# Sheet1.net
KiCad netlist of a schematic drawn in Altium Designer
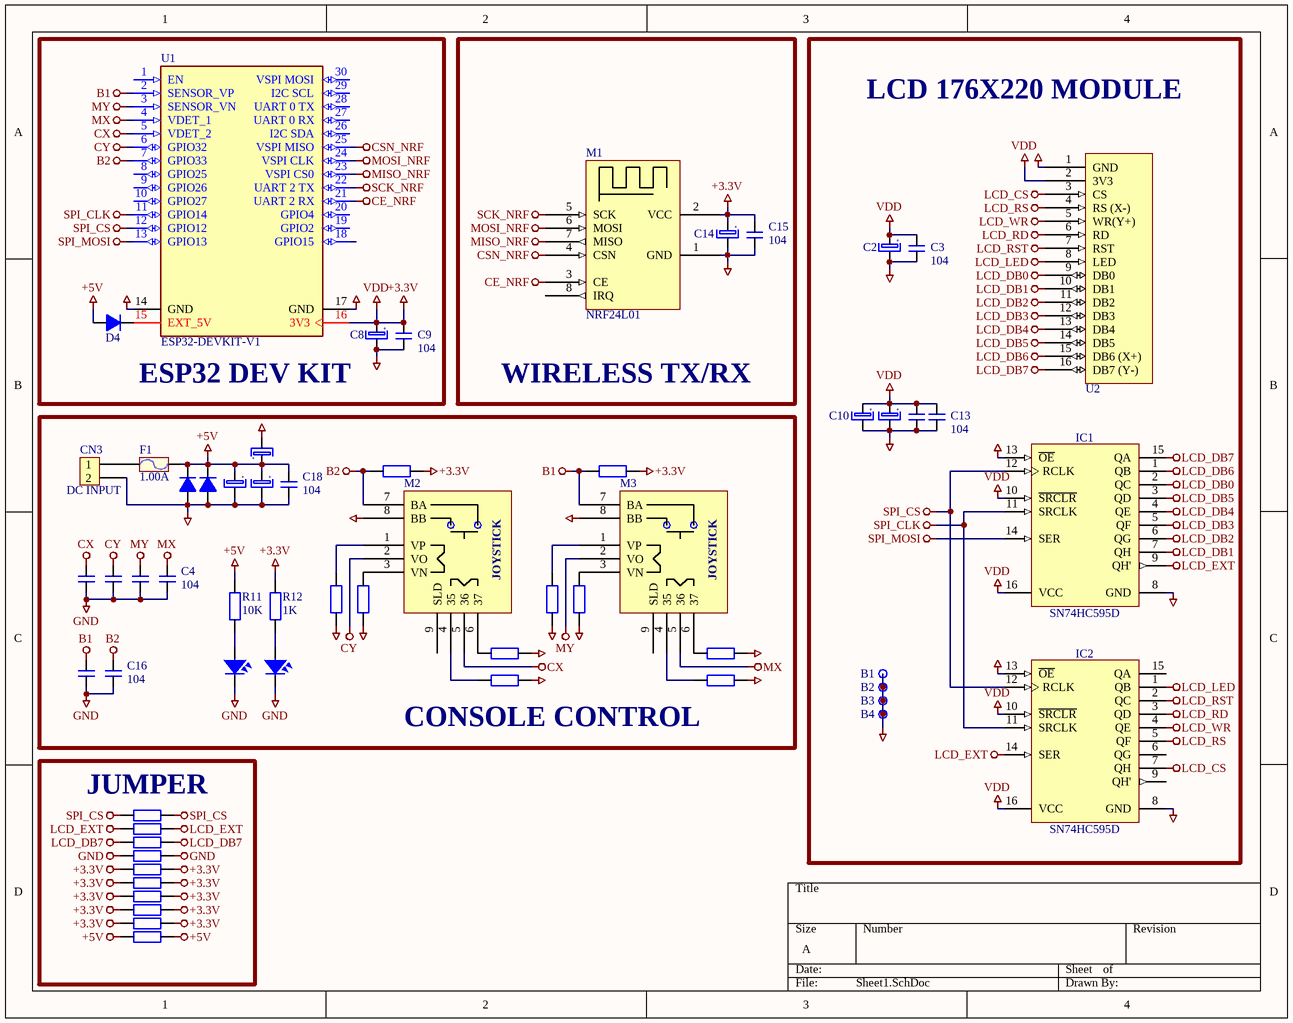
[diagram p0: Sheet1.SchDoc]

(export (version "E")
  (design (tool "Eeschema 10.0.6"))
  (components
    (comp (ref "B1")
      (value "Plated Hole")
      (footprint "MTG300_600")
      (description "Single Terminal Socket")
      (fields (field (name "PART NUMBER") "PLATED_HOLE3.0_PAD6.0") (field (name "AUTHOR") "CERN DEM JLC"))
      (libsource (lib "Eletro-mechanical") (part "Single Terminal Socket"))
    )
    (comp (ref "B2")
      (value "Plated Hole")
      (footprint "MTG300_600")
      (description "Single Terminal Socket")
      (fields (field (name "PART NUMBER") "PLATED_HOLE3.0_PAD6.0") (field (name "AUTHOR") "CERN DEM JLC"))
      (libsource (lib "Eletro-mechanical") (part "Single Terminal Socket"))
    )
    (comp (ref "B3")
      (value "Plated Hole")
      (footprint "MTG300_600")
      (description "Single Terminal Socket")
      (fields (field (name "PART NUMBER") "PLATED_HOLE3.0_PAD6.0") (field (name "AUTHOR") "CERN DEM JLC"))
      (libsource (lib "Eletro-mechanical") (part "Single Terminal Socket"))
    )
    (comp (ref "B4")
      (value "Plated Hole")
      (footprint "MTG300_600")
      (description "Single Terminal Socket")
      (fields (field (name "PART NUMBER") "PLATED_HOLE3.0_PAD6.0") (field (name "AUTHOR") "CERN DEM JLC"))
      (libsource (lib "Eletro-mechanical") (part "Single Terminal Socket"))
    )
    (comp (ref "C1")
      (value "470uF")
      (footprint "Cap-P-2.5/6.3")
      (description "Polarized capacitor")
      (libsource (lib "Library") (part "Cap-Pol-Dip"))
    )
    (comp (ref "C2")
      (value "220uF")
      (footprint "Cap-P-2.5/5")
      (description "Polarized capacitor")
      (libsource (lib "Library") (part "Cap-Pol-Dip"))
    )
    (comp (ref "C3")
      (value "104")
      (footprint "Cap-Non-150mil")
      (description "Non-polar capacitor")
      (libsource (lib "Library") (part "Cap-Non-Dip"))
    )
    (comp (ref "C4")
      (value "104")
      (footprint "CAP-SMD-0805")
      (description "Non-polar capacitor")
      (libsource (lib "Library") (part "Cap-Non-SMD"))
    )
    (comp (ref "C5")
      (value "104")
      (footprint "CAP-SMD-0805")
      (description "Non-polar capacitor")
      (libsource (lib "Library") (part "Cap-Non-SMD"))
    )
    (comp (ref "C6")
      (value "104")
      (footprint "CAP-SMD-0805")
      (description "Non-polar capacitor")
      (libsource (lib "Library") (part "Cap-Non-SMD"))
    )
    (comp (ref "C7")
      (value "104")
      (footprint "CAP-SMD-0805")
      (description "Non-polar capacitor")
      (libsource (lib "Library") (part "Cap-Non-SMD"))
    )
    (comp (ref "C8")
      (value "220uF")
      (footprint "Cap-P-2.5/5")
      (description "Polarized capacitor")
      (libsource (lib "Library") (part "Cap-Pol-Dip"))
    )
    (comp (ref "C9")
      (value "104")
      (footprint "Cap-Non-150mil")
      (description "Non-polar capacitor")
      (libsource (lib "Library") (part "Cap-Non-Dip"))
    )
    (comp (ref "C10")
      (value "220uF")
      (footprint "Cap-P-2.5/5")
      (description "Polarized capacitor")
      (libsource (lib "Library") (part "Cap-Pol-Dip"))
    )
    (comp (ref "C11")
      (value "220uF")
      (footprint "Cap-P-2.5/5")
      (description "Polarized capacitor")
      (libsource (lib "Library") (part "Cap-Pol-Dip"))
    )
    (comp (ref "C12")
      (value "104")
      (footprint "Cap-Non-150mil")
      (description "Non-polar capacitor")
      (libsource (lib "Library") (part "Cap-Non-Dip"))
    )
    (comp (ref "C13")
      (value "104")
      (footprint "Cap-Non-150mil")
      (description "Non-polar capacitor")
      (libsource (lib "Library") (part "Cap-Non-Dip"))
    )
    (comp (ref "C14")
      (value "220uF")
      (footprint "Cap-P-2.5/5")
      (description "Polarized capacitor")
      (libsource (lib "Library") (part "Cap-Pol-Dip"))
    )
    (comp (ref "C15")
      (value "104")
      (footprint "Cap-Non-150mil")
      (description "Non-polar capacitor")
      (libsource (lib "Library") (part "Cap-Non-Dip"))
    )
    (comp (ref "C16")
      (value "104")
      (footprint "CAP-SMD-0805")
      (description "Non-polar capacitor")
      (libsource (lib "Library") (part "Cap-Non-SMD"))
    )
    (comp (ref "C17")
      (value "104")
      (footprint "CAP-SMD-0805")
      (description "Non-polar capacitor")
      (libsource (lib "Library") (part "Cap-Non-SMD"))
    )
    (comp (ref "C18")
      (value "104")
      (footprint "Cap-Non-150mil")
      (description "Non-polar capacitor")
      (libsource (lib "Library") (part "Cap-Non-Dip"))
    )
    (comp (ref "C19")
      (value "470uF")
      (footprint "Cap-P-2.5/6.3")
      (description "Polarized capacitor")
      (libsource (lib "Library") (part "Cap-Pol-Dip"))
    )
    (comp (ref "C20")
      (value "470uF")
      (footprint "Cap-P-2.5/6.3")
      (description "Polarized capacitor")
      (libsource (lib "Library") (part "Cap-Pol-Dip"))
    )
    (comp (ref "CN3") (value "DC INPUT") (footprint "KF2/5.08") (libsource (lib "Library") (part "KF 2")))
    (comp (ref "D1")
      (value "SS14")
      (footprint "SOD 106")
      (description "Diode SMD")
      (libsource (lib "Library") (part "Diode SMD"))
    )
    (comp (ref "D2")
      (value "SS14")
      (footprint "SOD 106")
      (description "Diode SMD")
      (libsource (lib "Library") (part "Diode SMD"))
    )
    (comp (ref "D4")
      (value "SS14")
      (footprint "SOD 106")
      (description "Diode SMD")
      (libsource (lib "Library") (part "Diode SMD"))
    )
    (comp (ref "F1") (value "1.00A") (footprint "Fuse-Dip1") (libsource (lib "Library") (part "Fuse Dip")))
    (comp (ref "IC1")
      (value "SN74HC595D")
      (footprint "SOIC127P600X175-16N")
      (description "8-Bit Shift Register With 3-State Output Register")
      (fields (field (name "MANUFACTURER") "TEXAS INSTRUMENTS") (field (name "AUTHOR") "CERN DEM JLC"))
      (libsource (lib "ICs And Semiconductors") (part "74595"))
    )
    (comp (ref "IC2")
      (value "SN74HC595D")
      (footprint "SOIC127P600X175-16N")
      (description "8-Bit Shift Register With 3-State Output Register")
      (fields (field (name "MANUFACTURER") "TEXAS INSTRUMENTS") (field (name "AUTHOR") "CERN DEM JLC"))
      (libsource (lib "ICs And Semiconductors") (part "74595"))
    )
    (comp (ref "LED1") (value "POWER") (footprint "LED-0805") (libsource (lib "Library") (part "LED_SMD")))
    (comp (ref "LED2") (value "ESP-3.3V") (footprint "LED-0805") (libsource (lib "Library") (part "LED_SMD")))
    (comp (ref "M1")
      (value "NRF24L01")
      (footprint "NRF24L01P_M")
      (libsource (lib "TOAN_VERSION_1_0") (part "NRF24L01"))
    )
    (comp (ref "M2")
      (value "JOYSTICK")
      (footprint "JOYSTICK")
      (libsource (lib "TOAN_VERSION_1_0") (part "JOYSTICK"))
    )
    (comp (ref "M3")
      (value "JOYSTICK")
      (footprint "JOYSTICK")
      (libsource (lib "TOAN_VERSION_1_0") (part "JOYSTICK"))
    )
    (comp (ref "R1")
      (value "1K")
      (footprint "RES-SMD-0805")
      (description "Resistor SMD")
      (libsource (lib "Library") (part "Res SMD"))
    )
    (comp (ref "R2")
      (value "1K")
      (footprint "RES-SMD-0805")
      (description "Resistor SMD")
      (libsource (lib "Library") (part "Res SMD"))
    )
    (comp (ref "R3")
      (value "1K")
      (footprint "RES-SMD-0805")
      (description "Resistor SMD")
      (libsource (lib "Library") (part "Res SMD"))
    )
    (comp (ref "R4")
      (value "1K")
      (footprint "RES-SMD-0805")
      (description "Resistor SMD")
      (libsource (lib "Library") (part "Res SMD"))
    )
    (comp (ref "R5")
      (value "1K")
      (footprint "RES-SMD-0805")
      (description "Resistor SMD")
      (libsource (lib "Library") (part "Res SMD"))
    )
    (comp (ref "R6")
      (value "1K")
      (footprint "RES-SMD-0805")
      (description "Resistor SMD")
      (libsource (lib "Library") (part "Res SMD"))
    )
    (comp (ref "R7")
      (value "1K")
      (footprint "RES-SMD-0805")
      (description "Resistor SMD")
      (libsource (lib "Library") (part "Res SMD"))
    )
    (comp (ref "R8")
      (value "1K")
      (footprint "RES-SMD-0805")
      (description "Resistor SMD")
      (libsource (lib "Library") (part "Res SMD"))
    )
    (comp (ref "R9")
      (value "1K")
      (footprint "RES-SMD-0805")
      (description "Resistor SMD")
      (libsource (lib "Library") (part "Res SMD"))
    )
    (comp (ref "R10")
      (value "1K")
      (footprint "RES-SMD-0805")
      (description "Resistor SMD")
      (libsource (lib "Library") (part "Res SMD"))
    )
    (comp (ref "R11")
      (value "10K")
      (footprint "RES-SMD-0805")
      (description "Resistor SMD")
      (libsource (lib "Library") (part "Res SMD"))
    )
    (comp (ref "R12")
      (value "1K")
      (footprint "RES-SMD-0805")
      (description "Resistor SMD")
      (libsource (lib "Library") (part "Res SMD"))
    )
    (comp (ref "R13")
      (value "0R")
      (footprint "RES-SMD-0805")
      (description "Resistor SMD")
      (libsource (lib "Library") (part "Res SMD"))
    )
    (comp (ref "R14")
      (value "0R")
      (footprint "RES-SMD-0805")
      (description "Resistor SMD")
      (libsource (lib "Library") (part "Res SMD"))
    )
    (comp (ref "R15")
      (value "0R")
      (footprint "RES-SMD-0805")
      (description "Resistor SMD")
      (libsource (lib "Library") (part "Res SMD"))
    )
    (comp (ref "R16")
      (value "0R")
      (footprint "RES-SMD-1206")
      (description "Resistor SMD")
      (libsource (lib "Library") (part "Res SMD"))
    )
    (comp (ref "R17")
      (value "0R")
      (footprint "RES-SMD-1206")
      (description "Resistor SMD")
      (libsource (lib "Library") (part "Res SMD"))
    )
    (comp (ref "R18")
      (value "0R")
      (footprint "RES-SMD-1206")
      (description "Resistor SMD")
      (libsource (lib "Library") (part "Res SMD"))
    )
    (comp (ref "R19")
      (value "0R")
      (footprint "RES-SMD-2512")
      (description "Resistor SMD")
      (libsource (lib "Library") (part "Res SMD"))
    )
    (comp (ref "R20")
      (value "0R")
      (footprint "RES-SMD-2512")
      (description "Resistor SMD")
      (libsource (lib "Library") (part "Res SMD"))
    )
    (comp (ref "R21")
      (value "0R")
      (footprint "RES-SMD-2512")
      (description "Resistor SMD")
      (libsource (lib "Library") (part "Res SMD"))
    )
    (comp (ref "R22")
      (value "0R")
      (footprint "RES-SMD-2512")
      (description "Resistor SMD")
      (libsource (lib "Library") (part "Res SMD"))
    )
    (comp (ref "U1")
      (value "ESP32-DEVKIT-V1")
      (footprint "MODULE_ESP32-DEVKITC-32D")
      (fields (field (name "MF") "Espressif Systems") (field (name "MP") "ESP32-DEVKITC-32D"))
      (libsource (lib "TOAN_VERSION_1_0") (part "ESP32-DEVKIT-V1"))
    )
    (comp (ref "U2")
      (value "ST7775R_2.0")
      (footprint "LCD_176X220_MODULE")
      (libsource (lib "TOAN_VERSION_1_0") (part "LCD_176x220_ST7775R"))
    )
  )
  (nets
    (net (code "1") (name "+3.3V") (class "Default")
      (node (ref "C10") (pin "1") (pinfunction "1_1") (pintype "passive"))
      (node (ref "C11") (pin "1") (pinfunction "1_1") (pintype "passive"))
      (node (ref "C12") (pin "2") (pinfunction "2_2") (pintype "passive"))
      (node (ref "C13") (pin "2") (pinfunction "2_2") (pintype "passive"))
      (node (ref "C14") (pin "1") (pinfunction "1_1") (pintype "passive"))
      (node (ref "C15") (pin "2") (pinfunction "2_2") (pintype "passive"))
      (node (ref "C2") (pin "1") (pinfunction "1_1") (pintype "passive"))
      (node (ref "C3") (pin "2") (pinfunction "2_2") (pintype "passive"))
      (node (ref "C8") (pin "1") (pinfunction "1_1") (pintype "passive"))
      (node (ref "C9") (pin "2") (pinfunction "2_2") (pintype "passive"))
      (node (ref "IC1") (pin "10") (pinfunction "~{SRCLR}_10") (pintype "input"))
      (node (ref "IC1") (pin "16") (pinfunction "VCC_16") (pintype "power_in"))
      (node (ref "IC2") (pin "10") (pinfunction "~{SRCLR}_10") (pintype "input"))
      (node (ref "IC2") (pin "16") (pinfunction "VCC_16") (pintype "power_in"))
      (node (ref "M1") (pin "2") (pinfunction "VCC_2") (pintype "passive"))
      (node (ref "R1") (pin "2") (pinfunction "2_2") (pintype "passive"))
      (node (ref "R12") (pin "2") (pinfunction "2_2") (pintype "passive"))
      (node (ref "R17") (pin "1") (pinfunction "1_1") (pintype "passive"))
      (node (ref "R17") (pin "2") (pinfunction "2_2") (pintype "passive"))
      (node (ref "R18") (pin "1") (pinfunction "1_1") (pintype "passive"))
      (node (ref "R18") (pin "2") (pinfunction "2_2") (pintype "passive"))
      (node (ref "R19") (pin "1") (pinfunction "1_1") (pintype "passive"))
      (node (ref "R19") (pin "2") (pinfunction "2_2") (pintype "passive"))
      (node (ref "R2") (pin "2") (pinfunction "2_2") (pintype "passive"))
      (node (ref "R20") (pin "1") (pinfunction "1_1") (pintype "passive"))
      (node (ref "R20") (pin "2") (pinfunction "2_2") (pintype "passive"))
      (node (ref "R21") (pin "1") (pinfunction "1_1") (pintype "passive"))
      (node (ref "R21") (pin "2") (pinfunction "2_2") (pintype "passive"))
      (node (ref "R4") (pin "1") (pinfunction "1_1") (pintype "passive"))
      (node (ref "R6") (pin "1") (pinfunction "1_1") (pintype "passive"))
      (node (ref "R7") (pin "1") (pinfunction "1_1") (pintype "passive"))
      (node (ref "R8") (pin "1") (pinfunction "1_1") (pintype "passive"))
      (node (ref "U1") (pin "16") (pinfunction "3V3_16") (pintype "power_in"))
      (node (ref "U2") (pin "2") (pinfunction "3V3_2") (pintype "power_in"))
    )
    (net (code "2") (name "+5V") (class "Default")
      (node (ref "C1") (pin "1") (pinfunction "1_1") (pintype "passive"))
      (node (ref "C18") (pin "2") (pinfunction "2_2") (pintype "passive"))
      (node (ref "C19") (pin "1") (pinfunction "1_1") (pintype "passive"))
      (node (ref "C20") (pin "1") (pinfunction "1_1") (pintype "passive"))
      (node (ref "D1") (pin "2") (pinfunction "K_2") (pintype "passive"))
      (node (ref "D2") (pin "2") (pinfunction "K_2") (pintype "passive"))
      (node (ref "D4") (pin "1") (pinfunction "A_1") (pintype "passive"))
      (node (ref "F1") (pin "2") (pinfunction "2_2") (pintype "passive"))
      (node (ref "R11") (pin "2") (pinfunction "2_2") (pintype "passive"))
      (node (ref "R22") (pin "1") (pinfunction "1_1") (pintype "passive"))
      (node (ref "R22") (pin "2") (pinfunction "2_2") (pintype "passive"))
    )
    (net (code "3") (name "B1") (class "Default")
      (node (ref "C17") (pin "2") (pinfunction "2_2") (pintype "passive"))
      (node (ref "M3") (pin "7") (pinfunction "BA_7") (pintype "passive"))
      (node (ref "R2") (pin "1") (pinfunction "1_1") (pintype "passive"))
      (node (ref "U1") (pin "2") (pinfunction "SENSOR_VP_2") (pintype "input"))
    )
    (net (code "4") (name "B2") (class "Default")
      (node (ref "C16") (pin "2") (pinfunction "2_2") (pintype "passive"))
      (node (ref "M2") (pin "7") (pinfunction "BA_7") (pintype "passive"))
      (node (ref "R1") (pin "1") (pinfunction "1_1") (pintype "passive"))
      (node (ref "U1") (pin "7") (pinfunction "GPIO33_7") (pintype "bidirectional"))
    )
    (net (code "5") (name "CE_NRF") (class "Default")
      (node (ref "M1") (pin "3") (pinfunction "CE_3") (pintype "input"))
      (node (ref "U1") (pin "21") (pinfunction "UART_2_RX_21") (pintype "bidirectional"))
    )
    (net (code "6") (name "CSN_NRF") (class "Default")
      (node (ref "M1") (pin "4") (pinfunction "CSN_4") (pintype "input"))
      (node (ref "U1") (pin "25") (pinfunction "VSPI_MISO_25") (pintype "bidirectional"))
    )
    (net (code "7") (name "CX") (class "Default")
      (node (ref "C5") (pin "2") (pinfunction "2_2") (pintype "passive"))
      (node (ref "M2") (pin "5") (pinfunction "36_5") (pintype "passive"))
      (node (ref "U1") (pin "5") (pinfunction "VDET_2_5") (pintype "input"))
    )
    (net (code "8") (name "CY") (class "Default")
      (node (ref "C6") (pin "2") (pinfunction "2_2") (pintype "passive"))
      (node (ref "M2") (pin "2") (pinfunction "VO_2") (pintype "passive"))
      (node (ref "U1") (pin "6") (pinfunction "GPIO32_6") (pintype "bidirectional"))
    )
    (net (code "9") (name "GND") (class "Default")
      (node (ref "B1") (pin "1") (pinfunction "1_1") (pintype "bidirectional"))
      (node (ref "B2") (pin "1") (pinfunction "1_1") (pintype "bidirectional"))
      (node (ref "B3") (pin "1") (pinfunction "1_1") (pintype "bidirectional"))
      (node (ref "B4") (pin "1") (pinfunction "1_1") (pintype "bidirectional"))
      (node (ref "C1") (pin "2") (pinfunction "2_2") (pintype "passive"))
      (node (ref "C10") (pin "2") (pinfunction "2_2") (pintype "passive"))
      (node (ref "C11") (pin "2") (pinfunction "2_2") (pintype "passive"))
      (node (ref "C12") (pin "1") (pinfunction "1_1") (pintype "passive"))
      (node (ref "C13") (pin "1") (pinfunction "1_1") (pintype "passive"))
      (node (ref "C14") (pin "2") (pinfunction "2_2") (pintype "passive"))
      (node (ref "C15") (pin "1") (pinfunction "1_1") (pintype "passive"))
      (node (ref "C16") (pin "1") (pinfunction "1_1") (pintype "passive"))
      (node (ref "C17") (pin "1") (pinfunction "1_1") (pintype "passive"))
      (node (ref "C18") (pin "1") (pinfunction "1_1") (pintype "passive"))
      (node (ref "C19") (pin "2") (pinfunction "2_2") (pintype "passive"))
      (node (ref "C2") (pin "2") (pinfunction "2_2") (pintype "passive"))
      (node (ref "C20") (pin "2") (pinfunction "2_2") (pintype "passive"))
      (node (ref "C3") (pin "1") (pinfunction "1_1") (pintype "passive"))
      (node (ref "C4") (pin "1") (pinfunction "1_1") (pintype "passive"))
      (node (ref "C5") (pin "1") (pinfunction "1_1") (pintype "passive"))
      (node (ref "C6") (pin "1") (pinfunction "1_1") (pintype "passive"))
      (node (ref "C7") (pin "1") (pinfunction "1_1") (pintype "passive"))
      (node (ref "C8") (pin "2") (pinfunction "2_2") (pintype "passive"))
      (node (ref "C9") (pin "1") (pinfunction "1_1") (pintype "passive"))
      (node (ref "CN3") (pin "2") (pinfunction "2_2") (pintype "passive"))
      (node (ref "D1") (pin "1") (pinfunction "A_1") (pintype "passive"))
      (node (ref "D2") (pin "1") (pinfunction "A_1") (pintype "passive"))
      (node (ref "IC1") (pin "13") (pinfunction "~{OE}_13") (pintype "input"))
      (node (ref "IC1") (pin "8") (pinfunction "GND_8") (pintype "power_in"))
      (node (ref "IC2") (pin "13") (pinfunction "~{OE}_13") (pintype "input"))
      (node (ref "IC2") (pin "8") (pinfunction "GND_8") (pintype "power_in"))
      (node (ref "LED1") (pin "2") (pinfunction "2_2") (pintype "passive"))
      (node (ref "LED2") (pin "2") (pinfunction "2_2") (pintype "passive"))
      (node (ref "M1") (pin "1") (pinfunction "GND_1") (pintype "power_in"))
      (node (ref "M2") (pin "8") (pinfunction "BB_8") (pintype "passive"))
      (node (ref "M3") (pin "8") (pinfunction "BB_8") (pintype "passive"))
      (node (ref "R10") (pin "1") (pinfunction "1_1") (pintype "passive"))
      (node (ref "R16") (pin "1") (pinfunction "1_1") (pintype "passive"))
      (node (ref "R16") (pin "2") (pinfunction "2_2") (pintype "passive"))
      (node (ref "R3") (pin "1") (pinfunction "1_1") (pintype "passive"))
      (node (ref "R5") (pin "1") (pinfunction "1_1") (pintype "passive"))
      (node (ref "R9") (pin "1") (pinfunction "1_1") (pintype "passive"))
      (node (ref "U1") (pin "14") (pinfunction "GND_14") (pintype "power_in"))
      (node (ref "U1") (pin "17") (pinfunction "GND_17") (pintype "power_in"))
      (node (ref "U2") (pin "1") (pinfunction "GND_1") (pintype "power_in"))
    )
    (net (code "10") (name "LCD_CS") (class "Default")
      (node (ref "IC2") (pin "7") (pinfunction "QH_7") (pintype "tri_state"))
      (node (ref "U2") (pin "3") (pinfunction "CS_3") (pintype "input"))
    )
    (net (code "11") (name "LCD_DB0") (class "Default")
      (node (ref "IC1") (pin "2") (pinfunction "QC_2") (pintype "tri_state"))
      (node (ref "U2") (pin "9") (pinfunction "DB0_9") (pintype "bidirectional"))
    )
    (net (code "12") (name "LCD_DB1") (class "Default")
      (node (ref "IC1") (pin "7") (pinfunction "QH_7") (pintype "tri_state"))
      (node (ref "U2") (pin "10") (pinfunction "DB1_10") (pintype "bidirectional"))
    )
    (net (code "13") (name "LCD_DB2") (class "Default")
      (node (ref "IC1") (pin "6") (pinfunction "QG_6") (pintype "tri_state"))
      (node (ref "U2") (pin "11") (pinfunction "DB2_11") (pintype "bidirectional"))
    )
    (net (code "14") (name "LCD_DB3") (class "Default")
      (node (ref "IC1") (pin "5") (pinfunction "QF_5") (pintype "tri_state"))
      (node (ref "U2") (pin "12") (pinfunction "DB3_12") (pintype "bidirectional"))
    )
    (net (code "15") (name "LCD_DB4") (class "Default")
      (node (ref "IC1") (pin "4") (pinfunction "QE_4") (pintype "tri_state"))
      (node (ref "U2") (pin "13") (pinfunction "DB4_13") (pintype "bidirectional"))
    )
    (net (code "16") (name "LCD_DB5") (class "Default")
      (node (ref "IC1") (pin "3") (pinfunction "QD_3") (pintype "tri_state"))
      (node (ref "U2") (pin "14") (pinfunction "DB5_14") (pintype "bidirectional"))
    )
    (net (code "17") (name "LCD_DB6") (class "Default")
      (node (ref "IC1") (pin "1") (pinfunction "QB_1") (pintype "tri_state"))
      (node (ref "U2") (pin "15") (pinfunction "DB6_(X+)_15") (pintype "bidirectional"))
    )
    (net (code "18") (name "LCD_DB7") (class "Default")
      (node (ref "IC1") (pin "15") (pinfunction "QA_15") (pintype "tri_state"))
      (node (ref "R15") (pin "1") (pinfunction "1_1") (pintype "passive"))
      (node (ref "R15") (pin "2") (pinfunction "2_2") (pintype "passive"))
      (node (ref "U2") (pin "16") (pinfunction "DB7_(Y-)_16") (pintype "bidirectional"))
    )
    (net (code "19") (name "LCD_EXT") (class "Default")
      (node (ref "IC1") (pin "9") (pinfunction "QH'_9") (pintype "output"))
      (node (ref "IC2") (pin "14") (pinfunction "SER_14") (pintype "input"))
      (node (ref "R14") (pin "1") (pinfunction "1_1") (pintype "passive"))
      (node (ref "R14") (pin "2") (pinfunction "2_2") (pintype "passive"))
    )
    (net (code "20") (name "LCD_LED") (class "Default")
      (node (ref "IC2") (pin "1") (pinfunction "QB_1") (pintype "tri_state"))
      (node (ref "U2") (pin "8") (pinfunction "LED_8") (pintype "input"))
    )
    (net (code "21") (name "LCD_RD") (class "Default")
      (node (ref "IC2") (pin "3") (pinfunction "QD_3") (pintype "tri_state"))
      (node (ref "U2") (pin "6") (pinfunction "RD_6") (pintype "input"))
    )
    (net (code "22") (name "LCD_RS") (class "Default")
      (node (ref "IC2") (pin "5") (pinfunction "QF_5") (pintype "tri_state"))
      (node (ref "U2") (pin "4") (pinfunction "RS_(X-)_4") (pintype "input"))
    )
    (net (code "23") (name "LCD_RST") (class "Default")
      (node (ref "IC2") (pin "2") (pinfunction "QC_2") (pintype "tri_state"))
      (node (ref "U2") (pin "7") (pinfunction "RST_7") (pintype "input"))
    )
    (net (code "24") (name "LCD_WR") (class "Default")
      (node (ref "IC2") (pin "4") (pinfunction "QE_4") (pintype "tri_state"))
      (node (ref "U2") (pin "5") (pinfunction "WR(Y+)_5") (pintype "input"))
    )
    (net (code "25") (name "MISO_NRF") (class "Default")
      (node (ref "M1") (pin "7") (pinfunction "MISO_7") (pintype "output"))
      (node (ref "U1") (pin "23") (pinfunction "VSPI_CS0_23") (pintype "bidirectional"))
    )
    (net (code "26") (name "MOSI_NRF") (class "Default")
      (node (ref "M1") (pin "6") (pinfunction "MOSI_6") (pintype "input"))
      (node (ref "U1") (pin "24") (pinfunction "VSPI_CLK_24") (pintype "bidirectional"))
    )
    (net (code "27") (name "MX") (class "Default")
      (node (ref "C4") (pin "2") (pinfunction "2_2") (pintype "passive"))
      (node (ref "M3") (pin "5") (pinfunction "36_5") (pintype "passive"))
      (node (ref "U1") (pin "4") (pinfunction "VDET_1_4") (pintype "input"))
    )
    (net (code "28") (name "MY") (class "Default")
      (node (ref "C7") (pin "2") (pinfunction "2_2") (pintype "passive"))
      (node (ref "M3") (pin "2") (pinfunction "VO_2") (pintype "passive"))
      (node (ref "U1") (pin "3") (pinfunction "SENSOR_VN_3") (pintype "input"))
    )
    (net (code "29") (name "Net-(CN3-Pad1)") (class "Default")
      (node (ref "CN3") (pin "1") (pinfunction "1_1") (pintype "passive"))
      (node (ref "F1") (pin "1") (pinfunction "1_1") (pintype "passive"))
    )
    (net (code "30") (name "Net-(D4-K)") (class "Default")
      (node (ref "D4") (pin "2") (pinfunction "K_2") (pintype "passive"))
      (node (ref "U1") (pin "15") (pinfunction "EXT_5V_15") (pintype "power_in"))
    )
    (net (code "31") (name "Net-(LED1-Pad1)") (class "Default")
      (node (ref "LED1") (pin "1") (pinfunction "1_1") (pintype "passive"))
      (node (ref "R11") (pin "1") (pinfunction "1_1") (pintype "passive"))
    )
    (net (code "32") (name "Net-(LED2-Pad1)") (class "Default")
      (node (ref "LED2") (pin "1") (pinfunction "1_1") (pintype "passive"))
      (node (ref "R12") (pin "1") (pinfunction "1_1") (pintype "passive"))
    )
    (net (code "33") (name "Net-(M2-35)") (class "Default")
      (node (ref "M2") (pin "4") (pinfunction "35_4") (pintype "passive"))
      (node (ref "R9") (pin "2") (pinfunction "2_2") (pintype "passive"))
    )
    (net (code "34") (name "Net-(M2-37)") (class "Default")
      (node (ref "M2") (pin "6") (pinfunction "37_6") (pintype "passive"))
      (node (ref "R7") (pin "2") (pinfunction "2_2") (pintype "passive"))
    )
    (net (code "35") (name "Net-(M2-VN)") (class "Default")
      (node (ref "M2") (pin "3") (pinfunction "VN_3") (pintype "passive"))
      (node (ref "R4") (pin "2") (pinfunction "2_2") (pintype "passive"))
    )
    (net (code "36") (name "Net-(M2-VP)") (class "Default")
      (node (ref "M2") (pin "1") (pinfunction "VP_1") (pintype "passive"))
      (node (ref "R3") (pin "2") (pinfunction "2_2") (pintype "passive"))
    )
    (net (code "37") (name "Net-(M3-35)") (class "Default")
      (node (ref "M3") (pin "4") (pinfunction "35_4") (pintype "passive"))
      (node (ref "R10") (pin "2") (pinfunction "2_2") (pintype "passive"))
    )
    (net (code "38") (name "Net-(M3-37)") (class "Default")
      (node (ref "M3") (pin "6") (pinfunction "37_6") (pintype "passive"))
      (node (ref "R8") (pin "2") (pinfunction "2_2") (pintype "passive"))
    )
    (net (code "39") (name "Net-(M3-VN)") (class "Default")
      (node (ref "M3") (pin "3") (pinfunction "VN_3") (pintype "passive"))
      (node (ref "R6") (pin "2") (pinfunction "2_2") (pintype "passive"))
    )
    (net (code "40") (name "Net-(M3-VP)") (class "Default")
      (node (ref "M3") (pin "1") (pinfunction "VP_1") (pintype "passive"))
      (node (ref "R5") (pin "2") (pinfunction "2_2") (pintype "passive"))
    )
    (net (code "41") (name "SCK_NRF") (class "Default")
      (node (ref "M1") (pin "5") (pinfunction "SCK_5") (pintype "input"))
      (node (ref "U1") (pin "22") (pinfunction "UART_2_TX_22") (pintype "bidirectional"))
    )
    (net (code "42") (name "SPI_CLK") (class "Default")
      (node (ref "IC1") (pin "11") (pinfunction "SRCLK_11") (pintype "input"))
      (node (ref "IC2") (pin "11") (pinfunction "SRCLK_11") (pintype "input"))
      (node (ref "U1") (pin "11") (pinfunction "GPIO14_11") (pintype "bidirectional"))
    )
    (net (code "43") (name "SPI_CS") (class "Default")
      (node (ref "IC1") (pin "12") (pinfunction "RCLK_12") (pintype "input"))
      (node (ref "IC2") (pin "12") (pinfunction "RCLK_12") (pintype "input"))
      (node (ref "R13") (pin "1") (pinfunction "1_1") (pintype "passive"))
      (node (ref "R13") (pin "2") (pinfunction "2_2") (pintype "passive"))
      (node (ref "U1") (pin "12") (pinfunction "GPIO12_12") (pintype "bidirectional"))
    )
    (net (code "44") (name "SPI_MOSI") (class "Default")
      (node (ref "IC1") (pin "14") (pinfunction "SER_14") (pintype "input"))
      (node (ref "U1") (pin "13") (pinfunction "GPIO13_13") (pintype "bidirectional"))
    )
    (net (code "45") (name "unconnected-(IC2-QA-Pad15)") (class "Default")
      (node (ref "IC2") (pin "15") (pinfunction "QA_15") (pintype "tri_state"))
    )
    (net (code "46") (name "unconnected-(IC2-QG-Pad6)") (class "Default")
      (node (ref "IC2") (pin "6") (pinfunction "QG_6") (pintype "tri_state"))
    )
    (net (code "47") (name "unconnected-(IC2-QH'-Pad9)") (class "Default")
      (node (ref "IC2") (pin "9") (pinfunction "QH'_9") (pintype "output"))
    )
    (net (code "48") (name "unconnected-(M1-IRQ-Pad8)") (class "Default")
      (node (ref "M1") (pin "8") (pinfunction "IRQ_8") (pintype "output"))
    )
    (net (code "49") (name "unconnected-(M2-SLD-Pad9)") (class "Default")
      (node (ref "M2") (pin "9") (pinfunction "SLD_9") (pintype "passive"))
    )
    (net (code "50") (name "unconnected-(M3-SLD-Pad9)") (class "Default")
      (node (ref "M3") (pin "9") (pinfunction "SLD_9") (pintype "passive"))
    )
    (net (code "51") (name "unconnected-(U1-EN-Pad1)") (class "Default")
      (node (ref "U1") (pin "1") (pinfunction "EN_1") (pintype "input"))
    )
    (net (code "52") (name "unconnected-(U1-GPIO2-Pad19)") (class "Default")
      (node (ref "U1") (pin "19") (pinfunction "GPIO2_19") (pintype "bidirectional"))
    )
    (net (code "53") (name "unconnected-(U1-GPIO4-Pad20)") (class "Default")
      (node (ref "U1") (pin "20") (pinfunction "GPIO4_20") (pintype "bidirectional"))
    )
    (net (code "54") (name "unconnected-(U1-GPIO15-Pad18)") (class "Default")
      (node (ref "U1") (pin "18") (pinfunction "GPIO15_18") (pintype "bidirectional"))
    )
    (net (code "55") (name "unconnected-(U1-GPIO25-Pad8)") (class "Default")
      (node (ref "U1") (pin "8") (pinfunction "GPIO25_8") (pintype "bidirectional"))
    )
    (net (code "56") (name "unconnected-(U1-GPIO26-Pad9)") (class "Default")
      (node (ref "U1") (pin "9") (pinfunction "GPIO26_9") (pintype "bidirectional"))
    )
    (net (code "57") (name "unconnected-(U1-GPIO27-Pad10)") (class "Default")
      (node (ref "U1") (pin "10") (pinfunction "GPIO27_10") (pintype "bidirectional"))
    )
    (net (code "58") (name "unconnected-(U1-I2C_SCL-Pad29)") (class "Default")
      (node (ref "U1") (pin "29") (pinfunction "I2C_SCL_29") (pintype "bidirectional"))
    )
    (net (code "59") (name "unconnected-(U1-I2C_SDA-Pad26)") (class "Default")
      (node (ref "U1") (pin "26") (pinfunction "I2C_SDA_26") (pintype "bidirectional"))
    )
    (net (code "60") (name "unconnected-(U1-UART_0_RX-Pad27)") (class "Default")
      (node (ref "U1") (pin "27") (pinfunction "UART_0_RX_27") (pintype "bidirectional"))
    )
    (net (code "61") (name "unconnected-(U1-UART_0_TX-Pad28)") (class "Default")
      (node (ref "U1") (pin "28") (pinfunction "UART_0_TX_28") (pintype "bidirectional"))
    )
    (net (code "62") (name "unconnected-(U1-VSPI_MOSI-Pad30)") (class "Default")
      (node (ref "U1") (pin "30") (pinfunction "VSPI_MOSI_30") (pintype "bidirectional"))
    )
  )
)
